# llrf_afe_dds_clock.net
KiCad netlist of a schematic drawn in Altium Designer
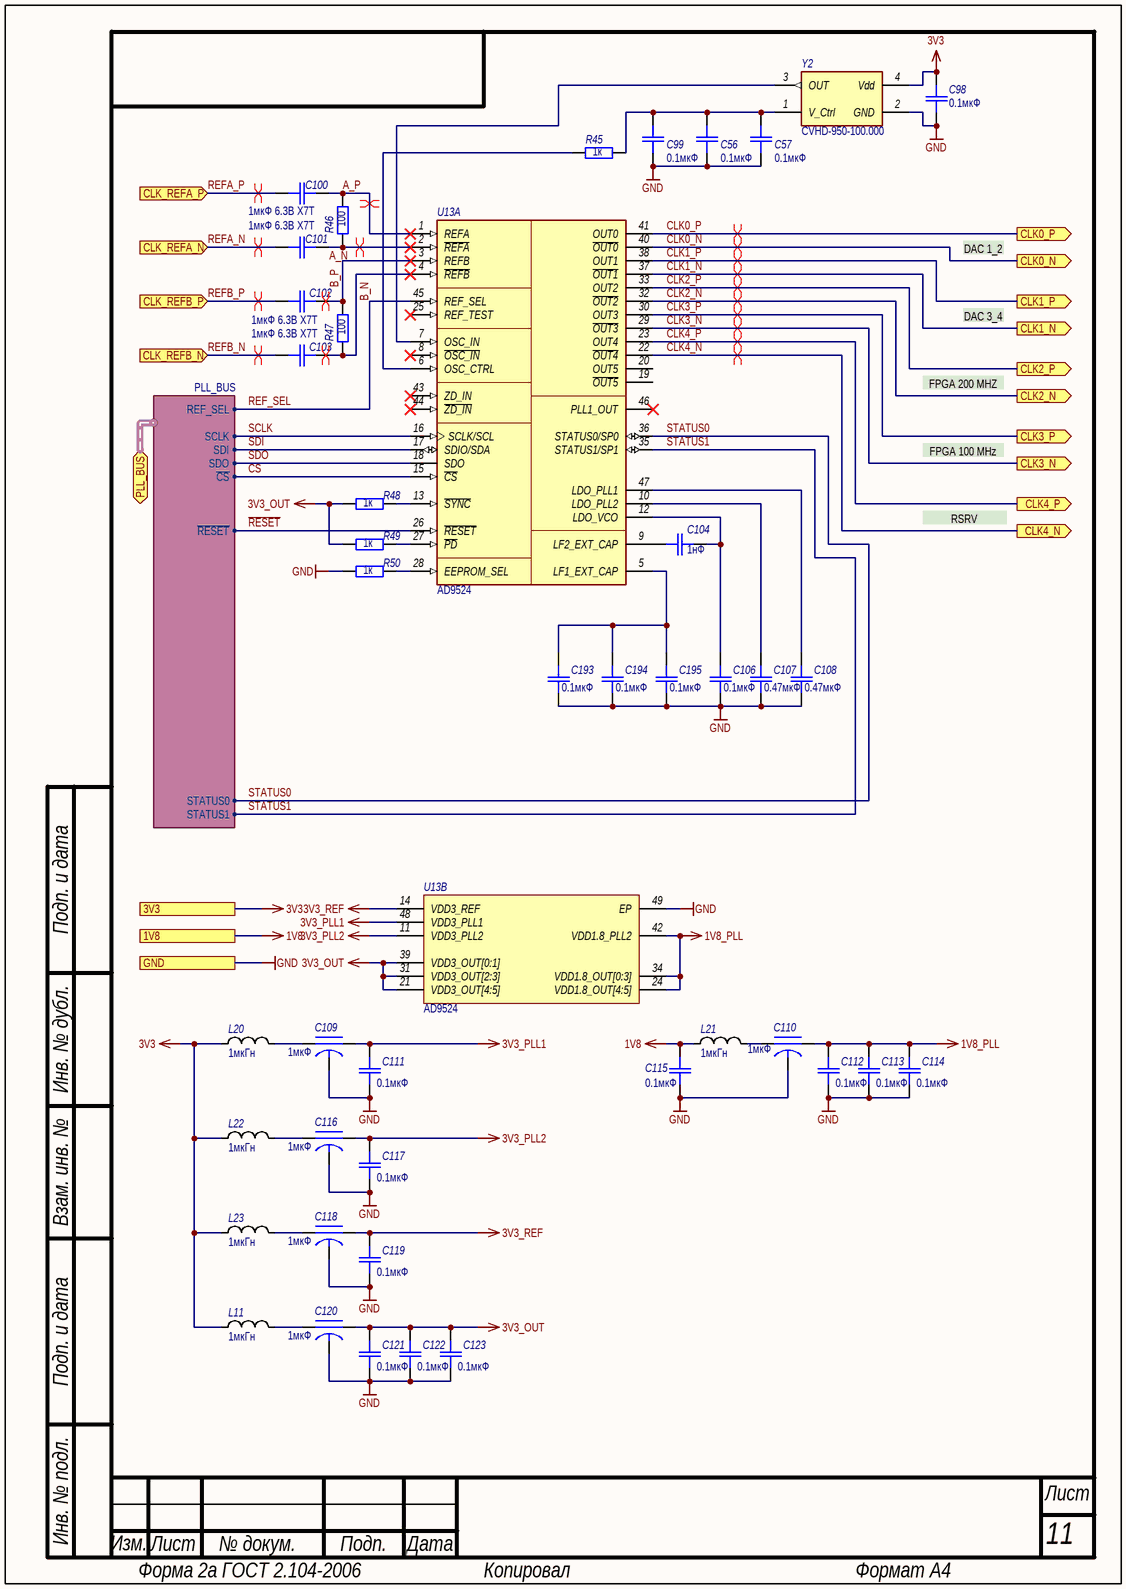
[diagram p0: llrf_afe_dds_clock.SchDoc]

(export (version "E")
  (design (tool "Eeschema 10.0.6"))
  (components
    (comp (ref "C56")
      (value "0.1мкФ")
      (footprint "SMD_C0603")
      (description "Capacitor")
      (libsource (lib "Passive") (part "Capacitor"))
    )
    (comp (ref "C57")
      (value "0.1мкФ")
      (footprint "SMD_C0603")
      (description "Capacitor")
      (libsource (lib "Passive") (part "Capacitor"))
    )
    (comp (ref "C98")
      (value "0.1мкФ")
      (footprint "SMD_C0402")
      (description "Capacitor")
      (libsource (lib "Passive") (part "Capacitor"))
    )
    (comp (ref "C99")
      (value "0.1мкФ")
      (footprint "SMD_C0603")
      (description "Capacitor")
      (libsource (lib "Passive") (part "Capacitor"))
    )
    (comp (ref "C100")
      (value "1мкФ 6.3В X7T")
      (footprint "SMD_C0603")
      (description "Capacitor")
      (libsource (lib "Passive") (part "Capacitor"))
    )
    (comp (ref "C101")
      (value "1мкФ 6.3В X7T")
      (footprint "SMD_C0603")
      (description "Capacitor")
      (libsource (lib "Passive") (part "Capacitor"))
    )
    (comp (ref "C102")
      (value "1мкФ 6.3В X7T")
      (footprint "SMD_C0603")
      (description "Capacitor")
      (libsource (lib "Passive") (part "Capacitor"))
    )
    (comp (ref "C103")
      (value "1мкФ 6.3В X7T")
      (footprint "SMD_C0603")
      (description "Capacitor")
      (libsource (lib "Passive") (part "Capacitor"))
    )
    (comp (ref "C104")
      (value "1нФ")
      (footprint "SMD_C0402")
      (description "Capacitor")
      (libsource (lib "Passive") (part "Capacitor"))
    )
    (comp (ref "C106")
      (value "0.1мкФ")
      (footprint "SMD_C0402")
      (description "Capacitor")
      (libsource (lib "Passive") (part "Capacitor"))
    )
    (comp (ref "C107")
      (value "0.47мкФ")
      (footprint "SMD_C0402")
      (description "Capacitor")
      (libsource (lib "Passive") (part "Capacitor"))
    )
    (comp (ref "C108")
      (value "0.47мкФ")
      (footprint "SMD_C0402")
      (description "Capacitor")
      (libsource (lib "Passive") (part "Capacitor"))
    )
    (comp (ref "C109")
      (value "1мкФ")
      (footprint "3pol_SMD0402")
      (fields (field (name "Comment") "NFM15PC105D0J3"))
      (libsource (lib "Capacitop_3Pol") (part "Capacitop_3Pol"))
    )
    (comp (ref "C110")
      (value "1мкФ")
      (footprint "3pol_SMD0402")
      (fields (field (name "Comment") "NFM15PC105D0J3"))
      (libsource (lib "Capacitop_3Pol") (part "Capacitop_3Pol"))
    )
    (comp (ref "C111")
      (value "0.1мкФ")
      (footprint "SMD_C0402")
      (description "Capacitor")
      (libsource (lib "Passive") (part "Capacitor"))
    )
    (comp (ref "C112")
      (value "0.1мкФ")
      (footprint "SMD_C0402")
      (description "Capacitor")
      (libsource (lib "Passive") (part "Capacitor"))
    )
    (comp (ref "C113")
      (value "0.1мкФ")
      (footprint "SMD_C0402")
      (description "Capacitor")
      (libsource (lib "Passive") (part "Capacitor"))
    )
    (comp (ref "C114")
      (value "0.1мкФ")
      (footprint "SMD_C0402")
      (description "Capacitor")
      (libsource (lib "Passive") (part "Capacitor"))
    )
    (comp (ref "C115")
      (value "0.1мкФ")
      (footprint "SMD_C0402")
      (description "Capacitor")
      (libsource (lib "Passive") (part "Capacitor"))
    )
    (comp (ref "C116")
      (value "1мкФ")
      (footprint "3pol_SMD0402")
      (fields (field (name "Comment") "NFM15PC105D0J3"))
      (libsource (lib "Capacitop_3Pol") (part "Capacitop_3Pol"))
    )
    (comp (ref "C117")
      (value "0.1мкФ")
      (footprint "SMD_C0402")
      (description "Capacitor")
      (libsource (lib "Passive") (part "Capacitor"))
    )
    (comp (ref "C118")
      (value "1мкФ")
      (footprint "3pol_SMD0402")
      (fields (field (name "Comment") "NFM15PC105D0J3"))
      (libsource (lib "Capacitop_3Pol") (part "Capacitop_3Pol"))
    )
    (comp (ref "C119")
      (value "0.1мкФ")
      (footprint "SMD_C0402")
      (description "Capacitor")
      (libsource (lib "Passive") (part "Capacitor"))
    )
    (comp (ref "C120")
      (value "1мкФ")
      (footprint "3pol_SMD0402")
      (fields (field (name "Comment") "NFM15PC105D0J3"))
      (libsource (lib "Capacitop_3Pol") (part "Capacitop_3Pol"))
    )
    (comp (ref "C121")
      (value "0.1мкФ")
      (footprint "SMD_C0402")
      (description "Capacitor")
      (libsource (lib "Passive") (part "Capacitor"))
    )
    (comp (ref "C122")
      (value "0.1мкФ")
      (footprint "SMD_C0402")
      (description "Capacitor")
      (libsource (lib "Passive") (part "Capacitor"))
    )
    (comp (ref "C123")
      (value "0.1мкФ")
      (footprint "SMD_C0402")
      (description "Capacitor")
      (libsource (lib "Passive") (part "Capacitor"))
    )
    (comp (ref "C193")
      (value "0.1мкФ")
      (footprint "SMD_C0402")
      (description "Capacitor")
      (libsource (lib "Passive") (part "Capacitor"))
    )
    (comp (ref "C194")
      (value "0.1мкФ")
      (footprint "SMD_C0402")
      (description "Capacitor")
      (libsource (lib "Passive") (part "Capacitor"))
    )
    (comp (ref "C195")
      (value "0.1мкФ")
      (footprint "SMD_C0402")
      (description "Capacitor")
      (libsource (lib "Passive") (part "Capacitor"))
    )
    (comp (ref "L11")
      (value "1мкГн")
      (footprint "SMD_0805")
      (description "Inductor")
      (libsource (lib "Passive") (part "Inductor"))
    )
    (comp (ref "L20")
      (value "1мкГн")
      (footprint "SMD_0805")
      (description "Inductor")
      (libsource (lib "Passive") (part "Inductor"))
    )
    (comp (ref "L21")
      (value "1мкГн")
      (footprint "SMD_0805")
      (description "Inductor")
      (libsource (lib "Passive") (part "Inductor"))
    )
    (comp (ref "L22")
      (value "1мкГн")
      (footprint "SMD_0805")
      (description "Inductor")
      (libsource (lib "Passive") (part "Inductor"))
    )
    (comp (ref "L23")
      (value "1мкГн")
      (footprint "SMD_0805")
      (description "Inductor")
      (libsource (lib "Passive") (part "Inductor"))
    )
    (comp (ref "R45")
      (value "1к")
      (footprint "SMD_0603")
      (description "Resistor")
      (libsource (lib "Passive") (part "Resistor"))
    )
    (comp (ref "R46")
      (value "100")
      (footprint "SMD_0603")
      (description "Resistor")
      (libsource (lib "") (part "Resistor_1"))
    )
    (comp (ref "R47")
      (value "100")
      (footprint "SMD_0603")
      (description "Resistor")
      (libsource (lib "") (part "Resistor_1"))
    )
    (comp (ref "R48")
      (value "1к")
      (footprint "SMD_0603")
      (description "Resistor")
      (libsource (lib "Passive") (part "Resistor"))
    )
    (comp (ref "R49")
      (value "1к")
      (footprint "SMD_0603")
      (description "Resistor")
      (libsource (lib "Passive") (part "Resistor"))
    )
    (comp (ref "R50")
      (value "1к")
      (footprint "SMD_0603")
      (description "Resistor")
      (libsource (lib "Passive") (part "Resistor"))
    )
    (comp (ref "U13")
      (value "AD9524BCPZ")
      (footprint "QFN-48")
      (fields
        (field (name "MANUFACTURER") "Analog Devices")
        (field (name "PARTNUMBER") "AD9524BCPZ-REEL7")
        (field (name "НАИМЕНОВАНИЕ") "AD9524")
      )
      (libsource (lib "AD9524") (part "AD9524"))
    )
    (comp (ref "Y2")
      (value "CVHD-950-100.000")
      (footprint "FP-CVHD-950")
      (description "XTAL OSC VCXO 50.0000MHZ CMOS")
      (fields
        (field (name "НАИМЕНОВАНИЕ") "CVHD-950-100.000")
        (field (name "MANUFACTURER") "Crystek Corporation")
        (field (name "MANUFACTURER PART NUMBER") "CVHD-950-50.000")
      )
      (libsource (lib "CVHD-950") (part "CVHD-950"))
    )
  )
  (nets
    (net (code "2") (name "/A_N") (class "Default")
      (node (ref "C101") (pin "2") (pinfunction "2_2") (pintype "passive"))
      (node (ref "R46") (pin "1") (pinfunction "1_1") (pintype "passive"))
      (node (ref "U13") (pin "2") (pinfunction "~{REFA}_2") (pintype "input"))
    )
    (net (code "3") (name "/A_P") (class "Default")
      (node (ref "C100") (pin "1") (pinfunction "1_1") (pintype "passive"))
      (node (ref "R46") (pin "2") (pinfunction "2_2") (pintype "passive"))
      (node (ref "U13") (pin "1") (pinfunction "REFA_1") (pintype "input"))
    )
    (net (code "4") (name "/B_N") (class "Default")
      (node (ref "C103") (pin "2") (pinfunction "2_2") (pintype "passive"))
      (node (ref "R47") (pin "1") (pinfunction "1_1") (pintype "passive"))
      (node (ref "U13") (pin "4") (pinfunction "~{REFB}_4") (pintype "input"))
    )
    (net (code "5") (name "/B_P") (class "Default")
      (node (ref "C102") (pin "1") (pinfunction "1_1") (pintype "passive"))
      (node (ref "R47") (pin "2") (pinfunction "2_2") (pintype "passive"))
      (node (ref "U13") (pin "3") (pinfunction "REFB_3") (pintype "input"))
    )
    (net (code "6") (name "/CLK0_N") (class "Default")
      (node (ref "U13") (pin "40") (pinfunction "~{OUT0}_40") (pintype "tri_state"))
    )
    (net (code "7") (name "/CLK0_P") (class "Default")
      (node (ref "U13") (pin "41") (pinfunction "OUT0_41") (pintype "tri_state"))
    )
    (net (code "8") (name "/CLK1_N") (class "Default")
      (node (ref "U13") (pin "37") (pinfunction "~{OUT1}_37") (pintype "tri_state"))
    )
    (net (code "9") (name "/CLK1_P") (class "Default")
      (node (ref "U13") (pin "38") (pinfunction "OUT1_38") (pintype "tri_state"))
    )
    (net (code "10") (name "/CLK2_N") (class "Default")
      (node (ref "U13") (pin "32") (pinfunction "~{OUT2}_32") (pintype "tri_state"))
    )
    (net (code "11") (name "/CLK2_P") (class "Default")
      (node (ref "U13") (pin "33") (pinfunction "OUT2_33") (pintype "tri_state"))
    )
    (net (code "12") (name "/CLK3_N") (class "Default")
      (node (ref "U13") (pin "29") (pinfunction "~{OUT3}_29") (pintype "tri_state"))
    )
    (net (code "13") (name "/CLK3_P") (class "Default")
      (node (ref "U13") (pin "30") (pinfunction "OUT3_30") (pintype "tri_state"))
    )
    (net (code "14") (name "/CLK4_N") (class "Default")
      (node (ref "U13") (pin "22") (pinfunction "~{OUT4}_22") (pintype "tri_state"))
    )
    (net (code "15") (name "/CLK4_P") (class "Default")
      (node (ref "U13") (pin "23") (pinfunction "OUT4_23") (pintype "tri_state"))
    )
    (net (code "16") (name "/REFA_N") (class "Default")
      (node (ref "C101") (pin "1") (pinfunction "1_1") (pintype "passive"))
    )
    (net (code "17") (name "/REFA_P") (class "Default")
      (node (ref "C100") (pin "2") (pinfunction "2_2") (pintype "passive"))
    )
    (net (code "18") (name "/REFB_N") (class "Default")
      (node (ref "C103") (pin "1") (pinfunction "1_1") (pintype "passive"))
    )
    (net (code "19") (name "/REFB_P") (class "Default")
      (node (ref "C102") (pin "2") (pinfunction "2_2") (pintype "passive"))
    )
    (net (code "20") (name "/REF_SEL") (class "Default")
      (node (ref "U13") (pin "45") (pinfunction "REF_SEL_45") (pintype "input"))
    )
    (net (code "21") (name "/SCLK") (class "Default")
      (node (ref "U13") (pin "16") (pinfunction "SCLK/SCL_16") (pintype "input"))
    )
    (net (code "22") (name "/SDI") (class "Default")
      (node (ref "U13") (pin "17") (pinfunction "SDIO/SDA_17") (pintype "bidirectional"))
    )
    (net (code "23") (name "/SDO") (class "Default")
      (node (ref "U13") (pin "18") (pinfunction "SDO_18") (pintype "tri_state"))
    )
    (net (code "24") (name "/STATUS0") (class "Default")
      (node (ref "U13") (pin "36") (pinfunction "STATUS0/SP0_36") (pintype "bidirectional"))
    )
    (net (code "25") (name "/STATUS1") (class "Default")
      (node (ref "U13") (pin "35") (pinfunction "STATUS1/SP1_35") (pintype "bidirectional"))
    )
    (net (code "27") (name "/~{CS}") (class "Default")
      (node (ref "U13") (pin "15") (pinfunction "~{CS}_15") (pintype "input"))
    )
    (net (code "28") (name "/~{RESET}") (class "Default")
      (node (ref "U13") (pin "26") (pinfunction "~{RESET}_26") (pintype "input"))
    )
    (net (code "29") (name "1V8") (class "Default")
      (node (ref "C115") (pin "2") (pinfunction "2_2") (pintype "passive"))
      (node (ref "L21") (pin "1") (pinfunction "1_1") (pintype "passive"))
    )
    (net (code "30") (name "1V8_PLL") (class "Default")
      (node (ref "C110") (pin "3") (pinfunction "Output_3") (pintype "passive"))
      (node (ref "C112") (pin "2") (pinfunction "2_2") (pintype "passive"))
      (node (ref "C113") (pin "2") (pinfunction "2_2") (pintype "passive"))
      (node (ref "C114") (pin "2") (pinfunction "2_2") (pintype "passive"))
      (node (ref "U13") (pin "24") (pinfunction "VDD1.8_OUT[4:5]_24") (pintype "power_in"))
      (node (ref "U13") (pin "34") (pinfunction "VDD1.8_OUT[0:3]_34") (pintype "power_in"))
      (node (ref "U13") (pin "42") (pinfunction "VDD1.8_PLL2_42") (pintype "power_in"))
    )
    (net (code "31") (name "3V3") (class "Default")
      (node (ref "C98") (pin "2") (pinfunction "2_2") (pintype "passive"))
      (node (ref "L11") (pin "1") (pinfunction "1_1") (pintype "passive"))
      (node (ref "L20") (pin "1") (pinfunction "1_1") (pintype "passive"))
      (node (ref "L22") (pin "1") (pinfunction "1_1") (pintype "passive"))
      (node (ref "L23") (pin "1") (pinfunction "1_1") (pintype "passive"))
      (node (ref "Y2") (pin "4") (pinfunction "Vdd_4") (pintype "power_in"))
    )
    (net (code "32") (name "3V3_OUT") (class "Default")
      (node (ref "C120") (pin "3") (pinfunction "Output_3") (pintype "passive"))
      (node (ref "C121") (pin "2") (pinfunction "2_2") (pintype "passive"))
      (node (ref "C122") (pin "2") (pinfunction "2_2") (pintype "passive"))
      (node (ref "C123") (pin "2") (pinfunction "2_2") (pintype "passive"))
      (node (ref "R48") (pin "2") (pinfunction "2_2") (pintype "passive"))
      (node (ref "R49") (pin "2") (pinfunction "2_2") (pintype "passive"))
      (node (ref "U13") (pin "21") (pinfunction "VDD3_OUT[4:5]_21") (pintype "power_in"))
      (node (ref "U13") (pin "31") (pinfunction "VDD3_OUT[2:3]_31") (pintype "power_in"))
      (node (ref "U13") (pin "39") (pinfunction "VDD3_OUT[0:1]_39") (pintype "power_in"))
    )
    (net (code "33") (name "3V3_PLL1") (class "Default")
      (node (ref "C109") (pin "3") (pinfunction "Output_3") (pintype "passive"))
      (node (ref "C111") (pin "2") (pinfunction "2_2") (pintype "passive"))
      (node (ref "U13") (pin "48") (pinfunction "VDD3_PLL1_48") (pintype "power_in"))
    )
    (net (code "34") (name "3V3_PLL2") (class "Default")
      (node (ref "C116") (pin "3") (pinfunction "Output_3") (pintype "passive"))
      (node (ref "C117") (pin "2") (pinfunction "2_2") (pintype "passive"))
      (node (ref "U13") (pin "11") (pinfunction "VDD3_PLL2_11") (pintype "power_in"))
    )
    (net (code "35") (name "3V3_REF") (class "Default")
      (node (ref "C118") (pin "3") (pinfunction "Output_3") (pintype "passive"))
      (node (ref "C119") (pin "2") (pinfunction "2_2") (pintype "passive"))
      (node (ref "U13") (pin "14") (pinfunction "VDD3_REF_14") (pintype "power_in"))
    )
    (net (code "36") (name "GND") (class "Default")
      (node (ref "C106") (pin "1") (pinfunction "1_1") (pintype "passive"))
      (node (ref "C107") (pin "1") (pinfunction "1_1") (pintype "passive"))
      (node (ref "C108") (pin "1") (pinfunction "1_1") (pintype "passive"))
      (node (ref "C109") (pin "2") (pinfunction "GND_2") (pintype "passive"))
      (node (ref "C110") (pin "2") (pinfunction "GND_2") (pintype "passive"))
      (node (ref "C111") (pin "1") (pinfunction "1_1") (pintype "passive"))
      (node (ref "C112") (pin "1") (pinfunction "1_1") (pintype "passive"))
      (node (ref "C113") (pin "1") (pinfunction "1_1") (pintype "passive"))
      (node (ref "C114") (pin "1") (pinfunction "1_1") (pintype "passive"))
      (node (ref "C115") (pin "1") (pinfunction "1_1") (pintype "passive"))
      (node (ref "C116") (pin "2") (pinfunction "GND_2") (pintype "passive"))
      (node (ref "C117") (pin "1") (pinfunction "1_1") (pintype "passive"))
      (node (ref "C118") (pin "2") (pinfunction "GND_2") (pintype "passive"))
      (node (ref "C119") (pin "1") (pinfunction "1_1") (pintype "passive"))
      (node (ref "C120") (pin "2") (pinfunction "GND_2") (pintype "passive"))
      (node (ref "C121") (pin "1") (pinfunction "1_1") (pintype "passive"))
      (node (ref "C122") (pin "1") (pinfunction "1_1") (pintype "passive"))
      (node (ref "C123") (pin "1") (pinfunction "1_1") (pintype "passive"))
      (node (ref "C193") (pin "1") (pinfunction "1_1") (pintype "passive"))
      (node (ref "C194") (pin "1") (pinfunction "1_1") (pintype "passive"))
      (node (ref "C195") (pin "1") (pinfunction "1_1") (pintype "passive"))
      (node (ref "C56") (pin "2") (pinfunction "2_2") (pintype "passive"))
      (node (ref "C57") (pin "2") (pinfunction "2_2") (pintype "passive"))
      (node (ref "C98") (pin "1") (pinfunction "1_1") (pintype "passive"))
      (node (ref "C99") (pin "2") (pinfunction "2_2") (pintype "passive"))
      (node (ref "R50") (pin "2") (pinfunction "2_2") (pintype "passive"))
      (node (ref "U13") (pin "49") (pinfunction "EP_49") (pintype "power_in"))
      (node (ref "Y2") (pin "2") (pinfunction "GND_2") (pintype "power_in"))
    )
    (net (code "37") (name "Net-(C109-Input)") (class "Default")
      (node (ref "C109") (pin "1") (pinfunction "Input_1") (pintype "passive"))
      (node (ref "L20") (pin "2") (pinfunction "2_2") (pintype "passive"))
    )
    (net (code "38") (name "Net-(C110-Input)") (class "Default")
      (node (ref "C110") (pin "1") (pinfunction "Input_1") (pintype "passive"))
      (node (ref "L21") (pin "2") (pinfunction "2_2") (pintype "passive"))
    )
    (net (code "39") (name "Net-(C116-Input)") (class "Default")
      (node (ref "C116") (pin "1") (pinfunction "Input_1") (pintype "passive"))
      (node (ref "L22") (pin "2") (pinfunction "2_2") (pintype "passive"))
    )
    (net (code "40") (name "Net-(C118-Input)") (class "Default")
      (node (ref "C118") (pin "1") (pinfunction "Input_1") (pintype "passive"))
      (node (ref "L23") (pin "2") (pinfunction "2_2") (pintype "passive"))
    )
    (net (code "41") (name "Net-(C120-Input)") (class "Default")
      (node (ref "C120") (pin "1") (pinfunction "Input_1") (pintype "passive"))
      (node (ref "L11") (pin "2") (pinfunction "2_2") (pintype "passive"))
    )
    (net (code "42") (name "Net-(U13A-EEPROM_SEL)") (class "Default")
      (node (ref "R50") (pin "1") (pinfunction "1_1") (pintype "passive"))
      (node (ref "U13") (pin "28") (pinfunction "EEPROM_SEL_28") (pintype "input"))
    )
    (net (code "43") (name "Net-(U13A-LDO_PLL1)") (class "Default")
      (node (ref "C108") (pin "2") (pinfunction "2_2") (pintype "passive"))
      (node (ref "U13") (pin "47") (pinfunction "LDO_PLL1_47") (pintype "passive"))
    )
    (net (code "44") (name "Net-(U13A-LDO_PLL2)") (class "Default")
      (node (ref "C107") (pin "2") (pinfunction "2_2") (pintype "passive"))
      (node (ref "U13") (pin "10") (pinfunction "LDO_PLL2_10") (pintype "passive"))
    )
    (net (code "45") (name "Net-(U13A-LDO_VCO)") (class "Default")
      (node (ref "C104") (pin "1") (pinfunction "1_1") (pintype "passive"))
      (node (ref "C106") (pin "2") (pinfunction "2_2") (pintype "passive"))
      (node (ref "U13") (pin "12") (pinfunction "LDO_VCO_12") (pintype "passive"))
    )
    (net (code "46") (name "Net-(U13A-LF1_EXT_CAP)") (class "Default")
      (node (ref "C193") (pin "2") (pinfunction "2_2") (pintype "passive"))
      (node (ref "C194") (pin "2") (pinfunction "2_2") (pintype "passive"))
      (node (ref "C195") (pin "2") (pinfunction "2_2") (pintype "passive"))
      (node (ref "U13") (pin "5") (pinfunction "LF1_EXT_CAP_5") (pintype "passive"))
    )
    (net (code "47") (name "Net-(U13A-LF2_EXT_CAP)") (class "Default")
      (node (ref "C104") (pin "2") (pinfunction "2_2") (pintype "passive"))
      (node (ref "U13") (pin "9") (pinfunction "LF2_EXT_CAP_9") (pintype "passive"))
    )
    (net (code "48") (name "Net-(U13A-OSC_CTRL)") (class "Default")
      (node (ref "R45") (pin "2") (pinfunction "2_2") (pintype "passive"))
      (node (ref "U13") (pin "6") (pinfunction "OSC_CTRL_6") (pintype "input"))
    )
    (net (code "49") (name "Net-(U13A-OSC_IN)") (class "Default")
      (node (ref "U13") (pin "7") (pinfunction "OSC_IN_7") (pintype "input"))
      (node (ref "Y2") (pin "3") (pinfunction "OUT_3") (pintype "output"))
    )
    (net (code "50") (name "Net-(U13A-~{PD})") (class "Default")
      (node (ref "R49") (pin "1") (pinfunction "1_1") (pintype "passive"))
      (node (ref "U13") (pin "27") (pinfunction "~{PD}_27") (pintype "input"))
    )
    (net (code "51") (name "Net-(U13A-~{SYNC})") (class "Default")
      (node (ref "R48") (pin "1") (pinfunction "1_1") (pintype "passive"))
      (node (ref "U13") (pin "13") (pinfunction "~{SYNC}_13") (pintype "input"))
    )
    (net (code "52") (name "Net-(Y2-V_Ctrl)") (class "Default")
      (node (ref "C56") (pin "1") (pinfunction "1_1") (pintype "passive"))
      (node (ref "C57") (pin "1") (pinfunction "1_1") (pintype "passive"))
      (node (ref "C99") (pin "1") (pinfunction "1_1") (pintype "passive"))
      (node (ref "R45") (pin "1") (pinfunction "1_1") (pintype "passive"))
      (node (ref "Y2") (pin "1") (pinfunction "V_Ctrl_1") (pintype "passive"))
    )
    (net (code "53") (name "unconnected-(U13A-OUT5-Pad20)") (class "Default")
      (node (ref "U13") (pin "20") (pinfunction "OUT5_20") (pintype "tri_state"))
    )
    (net (code "54") (name "unconnected-(U13A-PLL1_OUT-Pad46)") (class "Default")
      (node (ref "U13") (pin "46") (pinfunction "PLL1_OUT_46") (pintype "tri_state+no_connect"))
    )
    (net (code "55") (name "unconnected-(U13A-REF_TEST-Pad25)") (class "Default")
      (node (ref "U13") (pin "25") (pinfunction "REF_TEST_25") (pintype "input+no_connect"))
    )
    (net (code "56") (name "unconnected-(U13A-ZD_IN-Pad43)") (class "Default")
      (node (ref "U13") (pin "43") (pinfunction "ZD_IN_43") (pintype "input+no_connect"))
    )
    (net (code "57") (name "unconnected-(U13A-~{OSC_IN}-Pad8)") (class "Default")
      (node (ref "U13") (pin "8") (pinfunction "~{OSC_IN}_8") (pintype "input+no_connect"))
    )
    (net (code "58") (name "unconnected-(U13A-~{OUT5}-Pad19)") (class "Default")
      (node (ref "U13") (pin "19") (pinfunction "~{OUT5}_19") (pintype "tri_state"))
    )
    (net (code "59") (name "unconnected-(U13A-~{ZD_IN}-Pad44)") (class "Default")
      (node (ref "U13") (pin "44") (pinfunction "~{ZD_IN}_44") (pintype "input+no_connect"))
    )
  )
)
